# 15_-MCU_CONNECTORS.net
KiCad netlist of a schematic drawn in Altium Designer
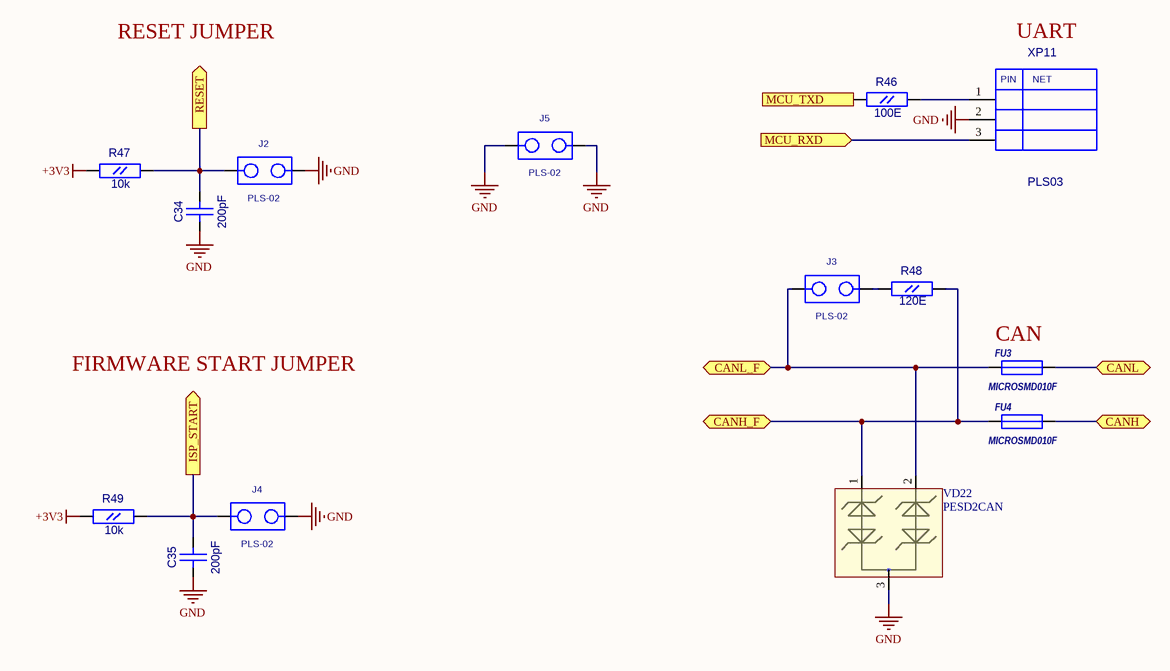
[diagram p0: [15]-MCU_CONNECTORS.SchDoc]

(export (version "E")
  (design (tool "Eeschema 10.0.6"))
  (components
    (comp (ref "C34")
      (value "200pF")
      (footprint "CC0603")
      (description "CC0603")
      (libsource (lib "gprs_modem_2") (part "CC0603"))
    )
    (comp (ref "C35")
      (value "200pF")
      (footprint "CC0603")
      (description "CC0603")
      (libsource (lib "gprs_modem_2") (part "CC0603"))
    )
    (comp (ref "FU3")
      (value "MICROSMD010F")
      (footprint "RC1210")
      (description "MICROSMD")
      (libsource (lib "gprs_modem_2") (part "MICROSMD"))
    )
    (comp (ref "FU4")
      (value "MICROSMD010F")
      (footprint "RC1210")
      (description "MICROSMD")
      (libsource (lib "gprs_modem_2") (part "MICROSMD"))
    )
    (comp (ref "J2") (value "PLS-02") (footprint "PLS-02") (libsource (lib "gprs_modem_2") (part "PLS-02")))
    (comp (ref "J3") (value "PLS-02") (footprint "PLS-02") (libsource (lib "fizik_lib") (part "PLS-02")))
    (comp (ref "J4") (value "PLS-02") (footprint "PLS-02") (libsource (lib "gprs_modem_2") (part "PLS-02")))
    (comp (ref "J5") (value "PLS-02") (footprint "PLS-02") (libsource (lib "gprs_modem_2") (part "PLS-02")))
    (comp (ref "R46")
      (value "100E")
      (footprint "RC0603")
      (description "RC0603")
      (libsource (lib "gprs_modem_2") (part "RC0603"))
    )
    (comp (ref "R47")
      (value "10k")
      (footprint "RC0603")
      (description "RC0603")
      (libsource (lib "gprs_modem_2") (part "RC0603"))
    )
    (comp (ref "R48")
      (value "120E")
      (footprint "RC0805")
      (description "RC0805")
      (libsource (lib "fizik_lib") (part "RC0805"))
    )
    (comp (ref "R49")
      (value "10k")
      (footprint "RC0603")
      (description "RC0603")
      (libsource (lib "gprs_modem_2") (part "RC0603"))
    )
    (comp (ref "VD22")
      (value "PESD2CAN")
      (footprint "SOT-23(123)")
      (description "TVS for CAN")
      (libsource (lib "gprs_modem_2") (part "PESD2CAN"))
    )
    (comp (ref "XP11") (value "PLS03") (footprint "PLS-03") (libsource (lib "fizik_lib") (part "PLS03")))
  )
  (nets
    (net (code "1") (name "+3V3") (class "Default")
      (node (ref "R47") (pin "1") (pinfunction "A_1") (pintype "passive"))
      (node (ref "R49") (pin "1") (pinfunction "A_1") (pintype "passive"))
    )
    (net (code "2") (name "/CANH") (class "Default") (node (ref "FU4") (pin "2") (pintype "passive")))
    (net (code "3") (name "/CANH_F") (class "Default")
      (node (ref "FU4") (pin "1") (pintype "passive"))
      (node (ref "R48") (pin "2") (pinfunction "B_2") (pintype "passive"))
      (node (ref "VD22") (pin "1") (pinfunction "1_1") (pintype "passive"))
    )
    (net (code "4") (name "/CANL") (class "Default") (node (ref "FU3") (pin "2") (pintype "passive")))
    (net (code "5") (name "/CANL_F") (class "Default")
      (node (ref "FU3") (pin "1") (pintype "passive"))
      (node (ref "J3") (pin "1") (pintype "passive"))
      (node (ref "VD22") (pin "2") (pinfunction "2_2") (pintype "passive"))
    )
    (net (code "6") (name "/ISP_START") (class "Default")
      (node (ref "C35") (pin "2") (pinfunction "B_2") (pintype "passive"))
      (node (ref "J4") (pin "1") (pintype "passive"))
      (node (ref "R49") (pin "2") (pinfunction "B_2") (pintype "passive"))
    )
    (net (code "7") (name "/MCU_RXD") (class "Default")
      (node (ref "XP11") (pin "3") (pinfunction "3_3") (pintype "passive"))
    )
    (net (code "8") (name "/MCU_TXD") (class "Default")
      (node (ref "R46") (pin "1") (pinfunction "A_1") (pintype "passive"))
    )
    (net (code "9") (name "/RESET") (class "Default")
      (node (ref "C34") (pin "2") (pinfunction "B_2") (pintype "passive"))
      (node (ref "J2") (pin "1") (pintype "passive"))
      (node (ref "R47") (pin "2") (pinfunction "B_2") (pintype "passive"))
    )
    (net (code "10") (name "GND") (class "Default")
      (node (ref "C34") (pin "1") (pinfunction "A_1") (pintype "passive"))
      (node (ref "C35") (pin "1") (pinfunction "A_1") (pintype "passive"))
      (node (ref "J2") (pin "2") (pintype "passive"))
      (node (ref "J4") (pin "2") (pintype "passive"))
      (node (ref "J5") (pin "1") (pintype "passive"))
      (node (ref "J5") (pin "2") (pintype "passive"))
      (node (ref "VD22") (pin "3") (pinfunction "3_3") (pintype "passive"))
      (node (ref "XP11") (pin "2") (pinfunction "2_2") (pintype "passive"))
    )
    (net (code "11") (name "Net-(R46-B)") (class "Default")
      (node (ref "R46") (pin "2") (pinfunction "B_2") (pintype "passive"))
      (node (ref "XP11") (pin "1") (pinfunction "1_1") (pintype "passive"))
    )
    (net (code "12") (name "Net-(R48-A)") (class "Default")
      (node (ref "J3") (pin "2") (pintype "passive"))
      (node (ref "R48") (pin "1") (pinfunction "A_1") (pintype "passive"))
    )
  )
)
